# etapa_4444.net
KiCad netlist of a schematic drawn in EAGLE
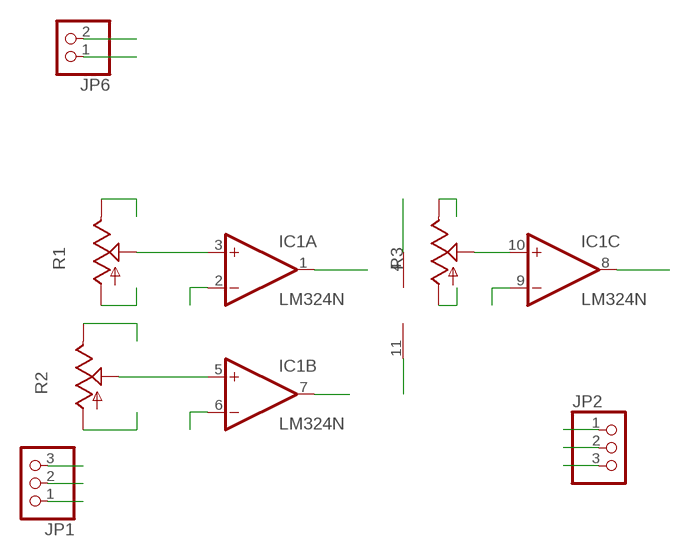
[diagram p0: schematic, sheet 1]

(export (version "E")
  (design (tool "Eeschema 10.0.6"))
  (components
    (comp (ref "IC1")
      (value "LM324N")
      (footprint "eagle-import:DIL14")
      (libsource (lib "eagle-import") (part "LM324N"))
    )
    (comp (ref "JP1")
      (value "PINHD-1X3")
      (footprint "eagle-import:1X03")
      (libsource (lib "eagle-import") (part "PINHD-1X3"))
    )
    (comp (ref "JP2")
      (value "PINHD-1X3")
      (footprint "eagle-import:1X03")
      (libsource (lib "eagle-import") (part "PINHD-1X3"))
    )
    (comp (ref "JP6")
      (value "PINHD-1X2")
      (footprint "eagle-import:1X02")
      (libsource (lib "eagle-import") (part "PINHD-1X2"))
    )
    (comp (ref "R1")
      (value "TRIM_US-S64W")
      (footprint "eagle-import:S64W")
      (libsource (lib "eagle-import") (part "TRIM_US-S64W"))
    )
    (comp (ref "R2")
      (value "TRIM_US-S64W")
      (footprint "eagle-import:S64W")
      (libsource (lib "eagle-import") (part "TRIM_US-S64W"))
    )
    (comp (ref "R3")
      (value "TRIM_US-S64W")
      (footprint "eagle-import:S64W")
      (libsource (lib "eagle-import") (part "TRIM_US-S64W"))
    )
  )
  (nets
    (net (code "1") (name "/FIL1") (class "Default")
      (node (ref "IC1") (pin "2") (pinfunction "-IN_2") (pintype "input"))
      (node (ref "JP1") (pin "2") (pinfunction "2_2") (pintype "passive"))
    )
    (net (code "2") (name "/FIL2") (class "Default")
      (node (ref "IC1") (pin "6") (pinfunction "-IN_6") (pintype "input"))
      (node (ref "JP1") (pin "3") (pinfunction "3_3") (pintype "passive"))
    )
    (net (code "3") (name "/FIL3") (class "Default")
      (node (ref "IC1") (pin "9") (pinfunction "-IN_9") (pintype "input"))
      (node (ref "JP1") (pin "1") (pinfunction "1_1") (pintype "passive"))
    )
    (net (code "4") (name "/GND") (class "Default")
      (node (ref "IC1") (pin "11") (pinfunction "V-_11") (pintype "power_in"))
      (node (ref "JP6") (pin "1") (pinfunction "1_1") (pintype "passive"))
      (node (ref "R1") (pin "A") (pinfunction "A_A") (pintype "passive"))
      (node (ref "R2") (pin "A") (pinfunction "A_A") (pintype "passive"))
      (node (ref "R3") (pin "A") (pinfunction "A_A") (pintype "passive"))
    )
    (net (code "5") (name "/OFIL1") (class "Default")
      (node (ref "IC1") (pin "1") (pinfunction "OUT_1") (pintype "output"))
      (node (ref "JP2") (pin "1") (pinfunction "1_1") (pintype "passive"))
    )
    (net (code "6") (name "/OFIL2") (class "Default")
      (node (ref "IC1") (pin "7") (pinfunction "OUT_7") (pintype "output"))
      (node (ref "JP2") (pin "2") (pinfunction "2_2") (pintype "passive"))
    )
    (net (code "7") (name "/OFIL3") (class "Default")
      (node (ref "IC1") (pin "8") (pinfunction "OUT_8") (pintype "output"))
      (node (ref "JP2") (pin "3") (pinfunction "3_3") (pintype "passive"))
    )
    (net (code "8") (name "/VCC") (class "Default")
      (node (ref "IC1") (pin "4") (pinfunction "V+_4") (pintype "power_in"))
      (node (ref "JP6") (pin "2") (pinfunction "2_2") (pintype "passive"))
      (node (ref "R1") (pin "E") (pinfunction "E_E") (pintype "passive"))
      (node (ref "R2") (pin "E") (pinfunction "E_E") (pintype "passive"))
      (node (ref "R3") (pin "E") (pinfunction "E_E") (pintype "passive"))
    )
    (net (code "9") (name "Net-(IC1A-+IN)") (class "Default")
      (node (ref "IC1") (pin "3") (pinfunction "+IN_3") (pintype "input"))
      (node (ref "R1") (pin "S") (pinfunction "S_S") (pintype "passive"))
    )
    (net (code "10") (name "Net-(IC1B-+IN)") (class "Default")
      (node (ref "IC1") (pin "5") (pinfunction "+IN_5") (pintype "input"))
      (node (ref "R2") (pin "S") (pinfunction "S_S") (pintype "passive"))
    )
    (net (code "11") (name "Net-(IC1C-+IN)") (class "Default")
      (node (ref "IC1") (pin "10") (pinfunction "+IN_10") (pintype "input"))
      (node (ref "R3") (pin "S") (pinfunction "S_S") (pintype "passive"))
    )
  )
)
